# power_board_pcie_-_v2.net
KiCad netlist of a schematic drawn in EAGLE
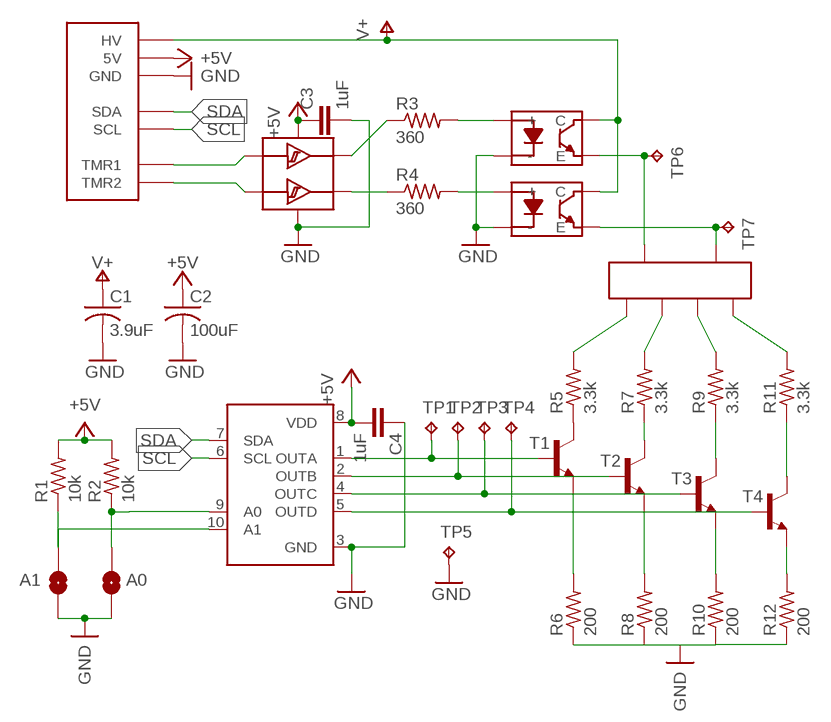
[diagram p0: schematic, sheet 1]

(export (version "E")
  (design (tool "Eeschema 10.0.6"))
  (components
    (comp (ref "A0")
      (value "JUMPER-SMT_2_NO_SILK_ROUND")
      (footprint "eagle-import:SMT-JUMPER_2_NO_SILK_ROUND")
      (libsource (lib "eagle-import") (part "JUMPER-SMT_2_NO_SILK_ROUND"))
    )
    (comp (ref "A1")
      (value "JUMPER-SMT_2_NO_SILK_ROUND")
      (footprint "eagle-import:SMT-JUMPER_2_NO_SILK_ROUND")
      (libsource (lib "eagle-import") (part "JUMPER-SMT_2_NO_SILK_ROUND"))
    )
    (comp (ref "C1")
      (value "3.9uF")
      (footprint "eagle-import:CAPAE830X1030")
      (libsource (lib "eagle-import") (part "UUX2D3R9MNL1GS"))
    )
    (comp (ref "C2")
      (value "100uF")
      (footprint "eagle-import:CAPAE530X550")
      (libsource (lib "eagle-import") (part "UWR1A101MCL1GB"))
    )
    (comp (ref "C3")
      (value "1uF")
      (footprint "eagle-import:C1206")
      (libsource (lib "eagle-import") (part "C-EUC1206"))
    )
    (comp (ref "C4")
      (value "1uF")
      (footprint "eagle-import:C1206")
      (libsource (lib "eagle-import") (part "C-EUC1206"))
    )
    (comp (ref "J1")
      (value "PCIE_EDGE")
      (footprint "eagle-import:PCIE_EDGE")
      (libsource (lib "eagle-import") (part "PCIE_EDGE"))
    )
    (comp (ref "JP3")
      (value "POWER_EDGE")
      (footprint "eagle-import:POWER_EDGE")
      (libsource (lib "eagle-import") (part "POWER_EDGE"))
    )
    (comp (ref "R1")
      (value "10k")
      (footprint "eagle-import:R1206")
      (libsource (lib "eagle-import") (part "R-US_R1206"))
    )
    (comp (ref "R2")
      (value "10k")
      (footprint "eagle-import:R1206")
      (libsource (lib "eagle-import") (part "R-US_R1206"))
    )
    (comp (ref "R3")
      (value "360")
      (footprint "eagle-import:R1206")
      (libsource (lib "eagle-import") (part "R-US_R1206"))
    )
    (comp (ref "R4")
      (value "360")
      (footprint "eagle-import:R1206")
      (libsource (lib "eagle-import") (part "R-US_R1206"))
    )
    (comp (ref "R5")
      (value "3.3k")
      (footprint "eagle-import:R2512")
      (libsource (lib "eagle-import") (part "R-US_R2512"))
    )
    (comp (ref "R6")
      (value "200")
      (footprint "eagle-import:R1206")
      (libsource (lib "eagle-import") (part "R-US_R1206"))
    )
    (comp (ref "R7")
      (value "3.3k")
      (footprint "eagle-import:R2512")
      (libsource (lib "eagle-import") (part "R-US_R2512"))
    )
    (comp (ref "R8")
      (value "200")
      (footprint "eagle-import:R1206")
      (libsource (lib "eagle-import") (part "R-US_R1206"))
    )
    (comp (ref "R9")
      (value "3.3k")
      (footprint "eagle-import:R2512")
      (libsource (lib "eagle-import") (part "R-US_R2512"))
    )
    (comp (ref "R10")
      (value "200")
      (footprint "eagle-import:R1206")
      (libsource (lib "eagle-import") (part "R-US_R1206"))
    )
    (comp (ref "R11")
      (value "3.3k")
      (footprint "eagle-import:R2512")
      (libsource (lib "eagle-import") (part "R-US_R2512"))
    )
    (comp (ref "R12")
      (value "200")
      (footprint "eagle-import:R1206")
      (libsource (lib "eagle-import") (part "R-US_R1206"))
    )
    (comp (ref "T1")
      (value "MMBT4401LT1-NPN-SOT23-BEC")
      (footprint "eagle-import:SOT23-BEC")
      (libsource (lib "eagle-import") (part "-NPN-SOT23-BECMMBT4401LT1"))
    )
    (comp (ref "T2")
      (value "MMBT4401LT1-NPN-SOT23-BEC")
      (footprint "eagle-import:SOT23-BEC")
      (libsource (lib "eagle-import") (part "-NPN-SOT23-BECMMBT4401LT1"))
    )
    (comp (ref "T3")
      (value "MMBT4401LT1-NPN-SOT23-BEC")
      (footprint "eagle-import:SOT23-BEC")
      (libsource (lib "eagle-import") (part "-NPN-SOT23-BECMMBT4401LT1"))
    )
    (comp (ref "T4")
      (value "MMBT4401LT1-NPN-SOT23-BEC")
      (footprint "eagle-import:SOT23-BEC")
      (libsource (lib "eagle-import") (part "-NPN-SOT23-BECMMBT4401LT1"))
    )
    (comp (ref "TP1")
      (value "TPB2,54")
      (footprint "eagle-import:B2,54")
      (libsource (lib "eagle-import") (part "TPB2,54"))
    )
    (comp (ref "TP2")
      (value "TPB2,54")
      (footprint "eagle-import:B2,54")
      (libsource (lib "eagle-import") (part "TPB2,54"))
    )
    (comp (ref "TP3")
      (value "TPB2,54")
      (footprint "eagle-import:B2,54")
      (libsource (lib "eagle-import") (part "TPB2,54"))
    )
    (comp (ref "TP4")
      (value "TPB2,54")
      (footprint "eagle-import:B2,54")
      (libsource (lib "eagle-import") (part "TPB2,54"))
    )
    (comp (ref "TP5")
      (value "TPB2,54")
      (footprint "eagle-import:B2,54")
      (libsource (lib "eagle-import") (part "TPB2,54"))
    )
    (comp (ref "TP6")
      (value "TPB2,54")
      (footprint "eagle-import:B2,54")
      (libsource (lib "eagle-import") (part "TPB2,54"))
    )
    (comp (ref "TP7")
      (value "TPB2,54")
      (footprint "eagle-import:B2,54")
      (libsource (lib "eagle-import") (part "TPB2,54"))
    )
    (comp (ref "U1")
      (value "TC7PZ17FU")
      (footprint "eagle-import:SOP65P210X100-6")
      (libsource (lib "eagle-import") (part "TC7PZ17FU"))
    )
    (comp (ref "U2")
      (value "DAC5574")
      (footprint "eagle-import:SOP50P490X110-10")
      (libsource (lib "eagle-import") (part "DAC5574"))
    )
    (comp (ref "U3")
      (value "LTV-352T")
      (footprint "eagle-import:SOP254P675X220-4")
      (libsource (lib "eagle-import") (part "LTV-352T"))
    )
    (comp (ref "U4")
      (value "LTV-352T")
      (footprint "eagle-import:SOP254P675X220-4")
      (libsource (lib "eagle-import") (part "LTV-352T"))
    )
  )
  (nets
    (net (code "1") (name "+5V") (class "Default")
      (node (ref "C2") (pin "1") (pinfunction "1_1") (pintype "passive"))
      (node (ref "C3") (pin "1") (pinfunction "1_1") (pintype "passive"))
      (node (ref "C4") (pin "2") (pinfunction "2_2") (pintype "passive"))
      (node (ref "J1") (pin "5V1") (pinfunction "5V_5V1") (pintype "passive"))
      (node (ref "J1") (pin "5V2") (pinfunction "5V_5V2") (pintype "passive"))
      (node (ref "R1") (pin "2") (pinfunction "2_2") (pintype "passive"))
      (node (ref "R2") (pin "2") (pinfunction "2_2") (pintype "passive"))
      (node (ref "U1") (pin "5") (pinfunction "VCC_5") (pintype "bidirectional"))
      (node (ref "U2") (pin "8") (pinfunction "VDD_8") (pintype "bidirectional"))
    )
    (net (code "2") (name "GND") (class "Default")
      (node (ref "A0") (pin "1") (pinfunction "1_1") (pintype "passive"))
      (node (ref "A1") (pin "1") (pinfunction "1_1") (pintype "passive"))
      (node (ref "C1") (pin "2") (pinfunction "2_2") (pintype "passive"))
      (node (ref "C2") (pin "2") (pinfunction "2_2") (pintype "passive"))
      (node (ref "C3") (pin "2") (pinfunction "2_2") (pintype "passive"))
      (node (ref "C4") (pin "1") (pinfunction "1_1") (pintype "passive"))
      (node (ref "J1") (pin "GND1") (pinfunction "GND_GND1") (pintype "passive"))
      (node (ref "J1") (pin "GND2") (pinfunction "GND_GND2") (pintype "passive"))
      (node (ref "R10") (pin "1") (pinfunction "1_1") (pintype "passive"))
      (node (ref "R12") (pin "1") (pinfunction "1_1") (pintype "passive"))
      (node (ref "R6") (pin "1") (pinfunction "1_1") (pintype "passive"))
      (node (ref "R8") (pin "1") (pinfunction "1_1") (pintype "passive"))
      (node (ref "TP5") (pin "TP") (pinfunction "TP_TP") (pintype "input"))
      (node (ref "U1") (pin "2") (pinfunction "GND_2") (pintype "bidirectional"))
      (node (ref "U2") (pin "3") (pinfunction "GND_3") (pintype "bidirectional"))
      (node (ref "U3") (pin "2") (pinfunction "-_2") (pintype "bidirectional"))
      (node (ref "U4") (pin "2") (pinfunction "-_2") (pintype "bidirectional"))
    )
    (net (code "3") (name "Net-(JP3-PadC1)") (class "Default")
      (node (ref "JP3") (pin "C1") (pinfunction "C1_C1") (pintype "bidirectional"))
      (node (ref "R5") (pin "2") (pinfunction "2_2") (pintype "passive"))
    )
    (net (code "4") (name "Net-(JP3-PadC2)") (class "Default")
      (node (ref "JP3") (pin "C2") (pinfunction "C2_C2") (pintype "bidirectional"))
      (node (ref "R7") (pin "2") (pinfunction "2_2") (pintype "passive"))
    )
    (net (code "5") (name "Net-(JP3-PadC3)") (class "Default")
      (node (ref "JP3") (pin "C3") (pinfunction "C3_C3") (pintype "bidirectional"))
      (node (ref "R9") (pin "2") (pinfunction "2_2") (pintype "passive"))
    )
    (net (code "6") (name "Net-(JP3-PadC4)") (class "Default")
      (node (ref "JP3") (pin "C4") (pinfunction "C4_C4") (pintype "bidirectional"))
      (node (ref "R11") (pin "2") (pinfunction "2_2") (pintype "passive"))
    )
    (net (code "7") (name "Net-(R5-Pad1)") (class "Default")
      (node (ref "R5") (pin "1") (pinfunction "1_1") (pintype "passive"))
      (node (ref "T1") (pin "C") (pinfunction "C_C") (pintype "passive"))
    )
    (net (code "8") (name "Net-(R6-Pad2)") (class "Default")
      (node (ref "R6") (pin "2") (pinfunction "2_2") (pintype "passive"))
      (node (ref "T1") (pin "E") (pinfunction "E_E") (pintype "passive"))
    )
    (net (code "9") (name "Net-(R7-Pad1)") (class "Default")
      (node (ref "R7") (pin "1") (pinfunction "1_1") (pintype "passive"))
      (node (ref "T2") (pin "C") (pinfunction "C_C") (pintype "passive"))
    )
    (net (code "10") (name "Net-(R8-Pad2)") (class "Default")
      (node (ref "R8") (pin "2") (pinfunction "2_2") (pintype "passive"))
      (node (ref "T2") (pin "E") (pinfunction "E_E") (pintype "passive"))
    )
    (net (code "11") (name "Net-(R9-Pad1)") (class "Default")
      (node (ref "R9") (pin "1") (pinfunction "1_1") (pintype "passive"))
      (node (ref "T3") (pin "C") (pinfunction "C_C") (pintype "passive"))
    )
    (net (code "12") (name "Net-(R10-Pad2)") (class "Default")
      (node (ref "R10") (pin "2") (pinfunction "2_2") (pintype "passive"))
      (node (ref "T3") (pin "E") (pinfunction "E_E") (pintype "passive"))
    )
    (net (code "13") (name "Net-(R11-Pad1)") (class "Default")
      (node (ref "R11") (pin "1") (pinfunction "1_1") (pintype "passive"))
      (node (ref "T4") (pin "C") (pinfunction "C_C") (pintype "passive"))
    )
    (net (code "14") (name "Net-(R12-Pad2)") (class "Default")
      (node (ref "R12") (pin "2") (pinfunction "2_2") (pintype "passive"))
      (node (ref "T4") (pin "E") (pinfunction "E_E") (pintype "passive"))
    )
    (net (code "15") (name "Net-(U1-1A)") (class "Default")
      (node (ref "J1") (pin "TMR1_1") (pinfunction "TMR1_TMR1_1") (pintype "bidirectional"))
      (node (ref "J1") (pin "TMR1_2") (pinfunction "TMR1_TMR1_2") (pintype "bidirectional"))
      (node (ref "U1") (pin "1") (pinfunction "1A_1") (pintype "bidirectional"))
    )
    (net (code "16") (name "Net-(U1-1Y)") (class "Default")
      (node (ref "R3") (pin "1") (pinfunction "1_1") (pintype "passive"))
      (node (ref "U1") (pin "6") (pinfunction "1Y_6") (pintype "bidirectional"))
    )
    (net (code "17") (name "Net-(U1-2A)") (class "Default")
      (node (ref "J1") (pin "TMR2_1") (pinfunction "TMR2_TMR2_1") (pintype "bidirectional"))
      (node (ref "J1") (pin "TMR2_2") (pinfunction "TMR2_TMR2_2") (pintype "bidirectional"))
      (node (ref "U1") (pin "3") (pinfunction "2A_3") (pintype "bidirectional"))
    )
    (net (code "18") (name "Net-(U1-2Y)") (class "Default")
      (node (ref "R4") (pin "1") (pinfunction "1_1") (pintype "passive"))
      (node (ref "U1") (pin "4") (pinfunction "2Y_4") (pintype "bidirectional"))
    )
    (net (code "19") (name "Net-(U2-A0)") (class "Default")
      (node (ref "A0") (pin "2") (pinfunction "2_2") (pintype "passive"))
      (node (ref "R2") (pin "1") (pinfunction "1_1") (pintype "passive"))
      (node (ref "U2") (pin "9") (pinfunction "A0_9") (pintype "bidirectional"))
    )
    (net (code "20") (name "Net-(U2-A1)") (class "Default")
      (node (ref "A1") (pin "2") (pinfunction "2_2") (pintype "passive"))
      (node (ref "R1") (pin "1") (pinfunction "1_1") (pintype "passive"))
      (node (ref "U2") (pin "10") (pinfunction "A1_10") (pintype "bidirectional"))
    )
    (net (code "21") (name "Net-(U2-OUTA)") (class "Default")
      (node (ref "T1") (pin "B") (pinfunction "B_B") (pintype "passive"))
      (node (ref "TP1") (pin "TP") (pinfunction "TP_TP") (pintype "input"))
      (node (ref "U2") (pin "1") (pinfunction "OUTA_1") (pintype "bidirectional"))
    )
    (net (code "22") (name "Net-(U2-OUTB)") (class "Default")
      (node (ref "T2") (pin "B") (pinfunction "B_B") (pintype "passive"))
      (node (ref "TP2") (pin "TP") (pinfunction "TP_TP") (pintype "input"))
      (node (ref "U2") (pin "2") (pinfunction "OUTB_2") (pintype "bidirectional"))
    )
    (net (code "23") (name "Net-(U2-OUTC)") (class "Default")
      (node (ref "T3") (pin "B") (pinfunction "B_B") (pintype "passive"))
      (node (ref "TP3") (pin "TP") (pinfunction "TP_TP") (pintype "input"))
      (node (ref "U2") (pin "4") (pinfunction "OUTC_4") (pintype "bidirectional"))
    )
    (net (code "24") (name "Net-(U2-OUTD)") (class "Default")
      (node (ref "T4") (pin "B") (pinfunction "B_B") (pintype "passive"))
      (node (ref "TP4") (pin "TP") (pinfunction "TP_TP") (pintype "input"))
      (node (ref "U2") (pin "5") (pinfunction "OUTD_5") (pintype "bidirectional"))
    )
    (net (code "25") (name "Net-(U3-+)") (class "Default")
      (node (ref "R3") (pin "2") (pinfunction "2_2") (pintype "passive"))
      (node (ref "U3") (pin "1") (pinfunction "+_1") (pintype "bidirectional"))
    )
    (net (code "26") (name "Net-(U3-E)") (class "Default")
      (node (ref "JP3") (pin "A1") (pinfunction "A1_A1") (pintype "bidirectional"))
      (node (ref "JP3") (pin "A2") (pinfunction "A1_A2") (pintype "bidirectional"))
      (node (ref "TP6") (pin "TP") (pinfunction "TP_TP") (pintype "input"))
      (node (ref "U3") (pin "3") (pinfunction "E_3") (pintype "bidirectional"))
    )
    (net (code "27") (name "Net-(U4-+)") (class "Default")
      (node (ref "R4") (pin "2") (pinfunction "2_2") (pintype "passive"))
      (node (ref "U4") (pin "1") (pinfunction "+_1") (pintype "bidirectional"))
    )
    (net (code "28") (name "Net-(U4-E)") (class "Default")
      (node (ref "JP3") (pin "A3") (pinfunction "A2_A3") (pintype "bidirectional"))
      (node (ref "JP3") (pin "A4") (pinfunction "A2_A4") (pintype "bidirectional"))
      (node (ref "TP7") (pin "TP") (pinfunction "TP_TP") (pintype "input"))
      (node (ref "U4") (pin "3") (pinfunction "E_3") (pintype "bidirectional"))
    )
    (net (code "29") (name "SCL") (class "Default")
      (node (ref "J1") (pin "SCL1") (pinfunction "SCL_SCL1") (pintype "bidirectional"))
      (node (ref "J1") (pin "SCL2") (pinfunction "SCL_SCL2") (pintype "bidirectional"))
      (node (ref "U2") (pin "6") (pinfunction "SCL_6") (pintype "bidirectional"))
    )
    (net (code "30") (name "SDA") (class "Default")
      (node (ref "J1") (pin "SDA1") (pinfunction "SDA_SDA1") (pintype "bidirectional"))
      (node (ref "J1") (pin "SDA2") (pinfunction "SDA_SDA2") (pintype "bidirectional"))
      (node (ref "U2") (pin "7") (pinfunction "SDA_7") (pintype "bidirectional"))
    )
    (net (code "31") (name "V+") (class "Default")
      (node (ref "C1") (pin "1") (pinfunction "1_1") (pintype "passive"))
      (node (ref "J1") (pin "HV1") (pinfunction "HV_HV1") (pintype "passive"))
      (node (ref "J1") (pin "HV2") (pinfunction "HV_HV2") (pintype "passive"))
      (node (ref "U3") (pin "4") (pinfunction "C_4") (pintype "bidirectional"))
      (node (ref "U4") (pin "4") (pinfunction "C_4") (pintype "bidirectional"))
    )
  )
)
